# Mach_trai_tim.net
KiCad netlist of a schematic drawn in Altium Designer
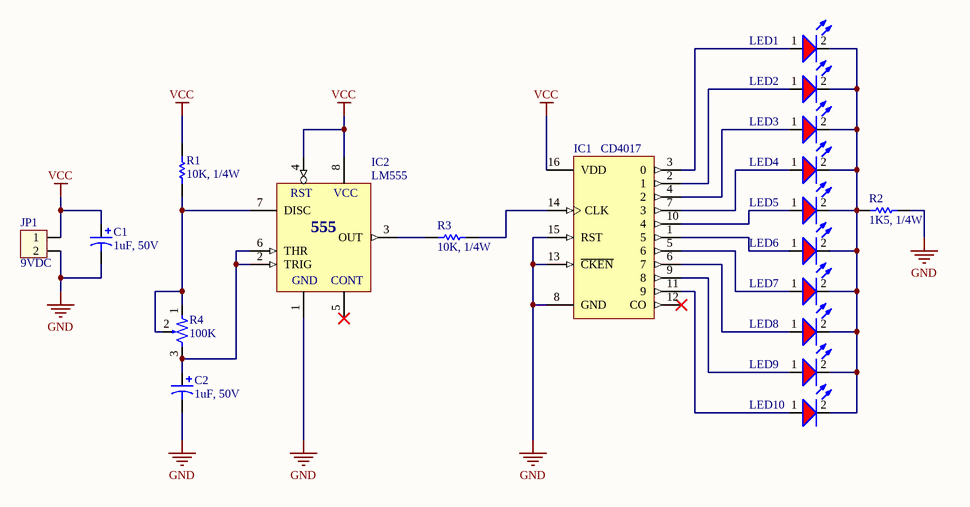
[diagram p0: Mach trai tim.SchDoc]

(export (version "E")
  (design (tool "Eeschema 10.0.6"))
  (components
    (comp (ref "C1")
      (value "1uF, 50V")
      (footprint "CAP_1UF_50V")
      (description "CAP GSR 0511 10uF 16V 20%")
      (fields (field (name "Comment") "GSR10M016-0511TAF"))
      (libsource (lib "lpson") (part "GSR10M016-0511TAF"))
    )
    (comp (ref "C2")
      (value "1uF, 50V")
      (footprint "CAP_1UF_50V")
      (description "CAP GSR 0511 10uF 16V 20%")
      (fields (field (name "Comment") "GSR10M016-0511TAF"))
      (libsource (lib "lpson") (part "GSR10M016-0511TAF"))
    )
    (comp (ref "IC1")
      (value "CD4017")
      (footprint "74HC4017")
      (description "Decade Counter/Divider with 10 Decoded Outputs")
      (fields
        (field (name "MANUFACTURER") "Texas Instruments")
        (field (name "MANUFACTURER PART NUMBER") "CD74HC4017E")
        (field (name "DESIGNED BY") "VanDungEvn")
      )
      (libsource (lib "lpson") (part "4017"))
    )
    (comp (ref "IC2")
      (value "LM555")
      (footprint "LM555")
      (description "Timer")
      (fields
        (field (name "MANUFACTURER") "Texas Instruments")
        (field (name "MANUFACTURER PART NUMBER") "NE555P")
      )
      (libsource (lib "lpson") (part "LM555"))
    )
    (comp (ref "JP1")
      (value "9VDC")
      (footprint "CON2")
      (description "Connector 2")
      (libsource (lib "lpson") (part "Con2"))
    )
    (comp (ref "LED1")
      (value "LED_R_5")
      (footprint "LED5R")
      (description "LED Red 5mm")
      (libsource (lib "lpson") (part "LED_RED_5MM"))
    )
    (comp (ref "LED2")
      (value "LED_R_5")
      (footprint "LED5R")
      (description "LED Red 5mm")
      (libsource (lib "lpson") (part "LED_RED_5MM"))
    )
    (comp (ref "LED3")
      (value "LED_R_5")
      (footprint "LED5R")
      (description "LED Red 5mm")
      (libsource (lib "lpson") (part "LED_RED_5MM"))
    )
    (comp (ref "LED4")
      (value "LED_R_5")
      (footprint "LED5R")
      (description "LED Red 5mm")
      (libsource (lib "lpson") (part "LED_RED_5MM"))
    )
    (comp (ref "LED5")
      (value "LED_R_5")
      (footprint "LED5R")
      (description "LED Red 5mm")
      (libsource (lib "lpson") (part "LED_RED_5MM"))
    )
    (comp (ref "LED6")
      (value "LED_R_5")
      (footprint "LED5R")
      (description "LED Red 5mm")
      (libsource (lib "lpson") (part "LED_RED_5MM"))
    )
    (comp (ref "LED7")
      (value "LED_R_5")
      (footprint "LED5R")
      (description "LED Red 5mm")
      (libsource (lib "lpson") (part "LED_RED_5MM"))
    )
    (comp (ref "LED8")
      (value "LED_R_5")
      (footprint "LED5R")
      (description "LED Red 5mm")
      (libsource (lib "lpson") (part "LED_RED_5MM"))
    )
    (comp (ref "LED9")
      (value "LED_R_5")
      (footprint "LED5R")
      (description "LED Red 5mm")
      (libsource (lib "lpson") (part "LED_RED_5MM"))
    )
    (comp (ref "LED10")
      (value "LED_R_5")
      (footprint "LED5R")
      (description "LED Red 5mm")
      (libsource (lib "lpson") (part "LED_RED_5MM"))
    )
    (comp (ref "R1")
      (value "10K, 1/4W")
      (footprint "RES 1/4W CFR25")
      (description "RES CF AXIAL-0.3 5% 1/4W 1K")
      (fields (field (name "Comment") "CF1/4W1KJ25"))
      (libsource (lib "lpson") (part "CF1/4W1KJ25"))
    )
    (comp (ref "R2")
      (value "1K5, 1/4W")
      (footprint "RES 1/4W CFR25")
      (description "RES CF AXIAL-0.3 5% 1/4W 1K")
      (fields (field (name "Comment") "CF1/4W1KJ25"))
      (libsource (lib "lpson") (part "CF1/4W1KJ25"))
    )
    (comp (ref "R3")
      (value "10K, 1/4W")
      (footprint "RES 1/4W CFR25")
      (description "RES CF AXIAL-0.3 5% 1/4W 1K")
      (fields (field (name "Comment") "CF1/4W1KJ25"))
      (libsource (lib "lpson") (part "CF1/4W1KJ25"))
    )
    (comp (ref "R4")
      (value "100K")
      (footprint "VR1")
      (description "Var Resistor")
      (libsource (lib "lpson") (part "VR2"))
    )
  )
  (nets
    (net (code "1") (name "GND") (class "Default")
      (node (ref "C1") (pin "2") (pinfunction "2_2") (pintype "passive"))
      (node (ref "C2") (pin "2") (pinfunction "2_2") (pintype "passive"))
      (node (ref "IC1") (pin "13") (pinfunction "~{CKEN}_13") (pintype "input"))
      (node (ref "IC1") (pin "15") (pinfunction "RST_15") (pintype "input"))
      (node (ref "IC1") (pin "8") (pinfunction "GND_8") (pintype "power_in"))
      (node (ref "IC2") (pin "1") (pinfunction "GND_1") (pintype "power_in"))
      (node (ref "JP1") (pin "2") (pinfunction "2_2") (pintype "passive"))
      (node (ref "R2") (pin "1") (pinfunction "1_1") (pintype "passive"))
    )
    (net (code "2") (name "Net-(IC1-0)") (class "Default")
      (node (ref "IC1") (pin "3") (pinfunction "0_3") (pintype "output"))
      (node (ref "LED1") (pin "1") (pinfunction "A_1") (pintype "passive"))
    )
    (net (code "3") (name "Net-(IC1-1)") (class "Default")
      (node (ref "IC1") (pin "2") (pinfunction "1_2") (pintype "output"))
      (node (ref "LED2") (pin "1") (pinfunction "A_1") (pintype "passive"))
    )
    (net (code "4") (name "Net-(IC1-2)") (class "Default")
      (node (ref "IC1") (pin "4") (pinfunction "2_4") (pintype "output"))
      (node (ref "LED3") (pin "1") (pinfunction "A_1") (pintype "passive"))
    )
    (net (code "5") (name "Net-(IC1-3)") (class "Default")
      (node (ref "IC1") (pin "7") (pinfunction "3_7") (pintype "output"))
      (node (ref "LED4") (pin "1") (pinfunction "A_1") (pintype "passive"))
    )
    (net (code "6") (name "Net-(IC1-4)") (class "Default")
      (node (ref "IC1") (pin "10") (pinfunction "4_10") (pintype "output"))
      (node (ref "LED5") (pin "1") (pinfunction "A_1") (pintype "passive"))
    )
    (net (code "7") (name "Net-(IC1-5)") (class "Default")
      (node (ref "IC1") (pin "1") (pinfunction "5_1") (pintype "output"))
      (node (ref "LED6") (pin "1") (pinfunction "A_1") (pintype "passive"))
    )
    (net (code "8") (name "Net-(IC1-6)") (class "Default")
      (node (ref "IC1") (pin "5") (pinfunction "6_5") (pintype "output"))
      (node (ref "LED7") (pin "1") (pinfunction "A_1") (pintype "passive"))
    )
    (net (code "9") (name "Net-(IC1-7)") (class "Default")
      (node (ref "IC1") (pin "6") (pinfunction "7_6") (pintype "output"))
      (node (ref "LED8") (pin "1") (pinfunction "A_1") (pintype "passive"))
    )
    (net (code "10") (name "Net-(IC1-8)") (class "Default")
      (node (ref "IC1") (pin "9") (pinfunction "8_9") (pintype "output"))
      (node (ref "LED9") (pin "1") (pinfunction "A_1") (pintype "passive"))
    )
    (net (code "11") (name "Net-(IC1-9)") (class "Default")
      (node (ref "IC1") (pin "11") (pinfunction "9_11") (pintype "output"))
      (node (ref "LED10") (pin "1") (pinfunction "A_1") (pintype "passive"))
    )
    (net (code "12") (name "Net-(IC1-CLK)") (class "Default")
      (node (ref "IC1") (pin "14") (pinfunction "CLK_14") (pintype "input"))
      (node (ref "R3") (pin "1") (pinfunction "1_1") (pintype "passive"))
    )
    (net (code "13") (name "Net-(IC2-DISC)") (class "Default")
      (node (ref "IC2") (pin "7") (pinfunction "DISC_7") (pintype "open_collector"))
      (node (ref "R1") (pin "1") (pinfunction "1_1") (pintype "passive"))
      (node (ref "R4") (pin "1") (pinfunction "1_1") (pintype "passive"))
      (node (ref "R4") (pin "2") (pinfunction "2_2") (pintype "passive"))
    )
    (net (code "14") (name "Net-(IC2-OUT)") (class "Default")
      (node (ref "IC2") (pin "3") (pinfunction "OUT_3") (pintype "output"))
      (node (ref "R3") (pin "2") (pinfunction "2_2") (pintype "passive"))
    )
    (net (code "15") (name "Net-(IC2-THR)") (class "Default")
      (node (ref "C2") (pin "1") (pinfunction "1_1") (pintype "passive"))
      (node (ref "IC2") (pin "2") (pinfunction "TRIG_2") (pintype "input"))
      (node (ref "IC2") (pin "6") (pinfunction "THR_6") (pintype "input"))
      (node (ref "R4") (pin "3") (pinfunction "3_3") (pintype "passive"))
    )
    (net (code "16") (name "Net-(LED1-K)") (class "Default")
      (node (ref "LED1") (pin "2") (pinfunction "K_2") (pintype "passive"))
      (node (ref "LED10") (pin "2") (pinfunction "K_2") (pintype "passive"))
      (node (ref "LED2") (pin "2") (pinfunction "K_2") (pintype "passive"))
      (node (ref "LED3") (pin "2") (pinfunction "K_2") (pintype "passive"))
      (node (ref "LED4") (pin "2") (pinfunction "K_2") (pintype "passive"))
      (node (ref "LED5") (pin "2") (pinfunction "K_2") (pintype "passive"))
      (node (ref "LED6") (pin "2") (pinfunction "K_2") (pintype "passive"))
      (node (ref "LED7") (pin "2") (pinfunction "K_2") (pintype "passive"))
      (node (ref "LED8") (pin "2") (pinfunction "K_2") (pintype "passive"))
      (node (ref "LED9") (pin "2") (pinfunction "K_2") (pintype "passive"))
      (node (ref "R2") (pin "2") (pinfunction "2_2") (pintype "passive"))
    )
    (net (code "17") (name "VCC") (class "Default")
      (node (ref "C1") (pin "1") (pinfunction "1_1") (pintype "passive"))
      (node (ref "IC1") (pin "16") (pinfunction "VDD_16") (pintype "power_in"))
      (node (ref "IC2") (pin "4") (pinfunction "RST_4") (pintype "input"))
      (node (ref "IC2") (pin "8") (pinfunction "VCC_8") (pintype "power_in"))
      (node (ref "JP1") (pin "1") (pinfunction "1_1") (pintype "passive"))
      (node (ref "R1") (pin "2") (pinfunction "2_2") (pintype "passive"))
    )
    (net (code "18") (name "unconnected-(IC1-CO-Pad12)") (class "Default")
      (node (ref "IC1") (pin "12") (pinfunction "CO_12") (pintype "output+no_connect"))
    )
    (net (code "19") (name "unconnected-(IC2-CONT-Pad5)") (class "Default")
      (node (ref "IC2") (pin "5") (pinfunction "CONT_5") (pintype "passive+no_connect"))
    )
  )
)
